# CH340T3R-R0.net
KiCad netlist of a schematic drawn in Altium Designer
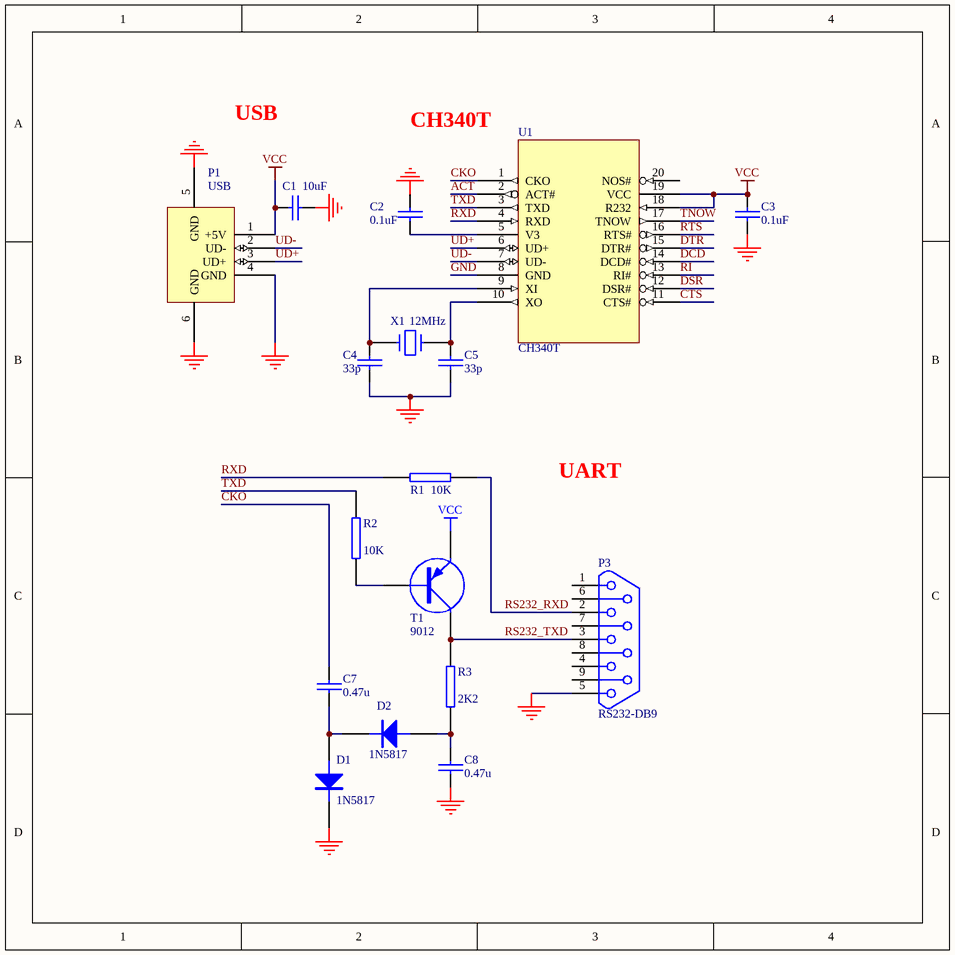
[diagram p0: CH340T3R-R0.SchDoc]

(export (version "E")
  (design (tool "Eeschema 10.0.6"))
  (components
    (comp (ref "C1")
      (value "10uF")
      (footprint "3216_C")
      (description "Capacitor")
      (libsource (lib "*") (part "CAP"))
    )
    (comp (ref "C2")
      (value "0.1uF")
      (footprint "0603_C")
      (description "Capacitor")
      (libsource (lib "*") (part "CAP"))
    )
    (comp (ref "C3")
      (value "0.1uF")
      (footprint "0603_C")
      (description "Capacitor")
      (libsource (lib "*") (part "CAP"))
    )
    (comp (ref "C4")
      (value "33p")
      (footprint "0603_C")
      (description "Capacitor")
      (libsource (lib "") (part "CAP_1"))
    )
    (comp (ref "C5")
      (value "33p")
      (footprint "0603_C")
      (description "Capacitor")
      (libsource (lib "") (part "CAP_1"))
    )
    (comp (ref "C7") (value "0.47u") (footprint "0603_C") (libsource (lib "*") (part "CPA")))
    (comp (ref "C8") (value "0.47u") (footprint "0603_C") (libsource (lib "*") (part "CPA")))
    (comp (ref "D1")
      (value "1N5817")
      (footprint "7227+")
      (description "Diode")
      (libsource (lib "*") (part "DIODE"))
    )
    (comp (ref "D2")
      (value "1N5817")
      (footprint "7227+")
      (description "Diode")
      (libsource (lib "*") (part "DIODE"))
    )
    (comp (ref "P1") (value "USB") (footprint "USBAM") (libsource (lib "*") (part "USB")))
    (comp (ref "P3")
      (value "RS232-DB9")
      (footprint "DB9-PAD-M")
      (libsource (lib "wch_sch_others") (part "DB9"))
    )
    (comp (ref "R1") (value "10K") (footprint "0603") (libsource (lib "*") (part "RES2")))
    (comp (ref "R2") (value "10K") (footprint "0603") (libsource (lib "*") (part "RES2")))
    (comp (ref "R3") (value "2K2") (footprint "0603") (libsource (lib "*") (part "RES2")))
    (comp (ref "T1")
      (value "9012")
      (footprint "SOT-23")
      (description "PNP Transistor")
      (libsource (lib "*") (part "PNP"))
    )
    (comp (ref "U1")
      (value "CH340T")
      (footprint "SSOP20")
      (description "USB to TTL Serial / UART,  USB to IrDA")
      (libsource (lib "CHXXX") (part "CH340T"))
    )
    (comp (ref "X1")
      (value "12MHz")
      (footprint "XT3225")
      (description "Crystal")
      (libsource (lib "*") (part "CRYSTAL"))
    )
  )
  (nets
    (net (code "1") (name "/ACT") (class "Default")
      (node (ref "U1") (pin "2") (pinfunction "ACT#_2") (pintype "output"))
    )
    (net (code "2") (name "/CKO") (class "Default")
      (node (ref "C7") (pin "2") (pintype "passive"))
      (node (ref "U1") (pin "1") (pinfunction "CKO_1") (pintype "output"))
    )
    (net (code "3") (name "/CTS") (class "Default")
      (node (ref "U1") (pin "11") (pinfunction "CTS#_11") (pintype "input"))
    )
    (net (code "4") (name "/DCD") (class "Default")
      (node (ref "U1") (pin "14") (pinfunction "DCD#_14") (pintype "input"))
    )
    (net (code "5") (name "/DSR") (class "Default")
      (node (ref "U1") (pin "12") (pinfunction "DSR#_12") (pintype "input"))
    )
    (net (code "6") (name "/DTR") (class "Default")
      (node (ref "U1") (pin "15") (pinfunction "DTR#_15") (pintype "output"))
    )
    (net (code "7") (name "/RI") (class "Default")
      (node (ref "U1") (pin "13") (pinfunction "RI#_13") (pintype "input"))
    )
    (net (code "8") (name "/RS232_RXD") (class "Default")
      (node (ref "P3") (pin "2") (pinfunction "2_2") (pintype "passive"))
      (node (ref "R1") (pin "2") (pinfunction "2_2") (pintype "passive"))
    )
    (net (code "9") (name "/RS232_TXD") (class "Default")
      (node (ref "P3") (pin "3") (pinfunction "3_3") (pintype "passive"))
      (node (ref "R3") (pin "2") (pinfunction "2_2") (pintype "passive"))
      (node (ref "T1") (pin "3") (pinfunction "C_3") (pintype "passive"))
    )
    (net (code "10") (name "/RTS") (class "Default")
      (node (ref "U1") (pin "16") (pinfunction "RTS#_16") (pintype "output"))
    )
    (net (code "11") (name "/RXD") (class "Default")
      (node (ref "R1") (pin "1") (pinfunction "1_1") (pintype "passive"))
      (node (ref "U1") (pin "4") (pinfunction "RXD_4") (pintype "input"))
    )
    (net (code "12") (name "/TNOW") (class "Default")
      (node (ref "U1") (pin "17") (pinfunction "TNOW_17") (pintype "output"))
    )
    (net (code "13") (name "/TXD") (class "Default")
      (node (ref "R2") (pin "2") (pinfunction "2_2") (pintype "passive"))
      (node (ref "U1") (pin "3") (pinfunction "TXD_3") (pintype "output"))
    )
    (net (code "14") (name "/UD+") (class "Default")
      (node (ref "P1") (pin "3") (pinfunction "UD+_3") (pintype "bidirectional"))
      (node (ref "U1") (pin "6") (pinfunction "UD+_6") (pintype "bidirectional"))
    )
    (net (code "15") (name "/UD-") (class "Default")
      (node (ref "P1") (pin "2") (pinfunction "UD-_2") (pintype "bidirectional"))
      (node (ref "U1") (pin "7") (pinfunction "UD-_7") (pintype "bidirectional"))
    )
    (net (code "16") (name "GND") (class "Default")
      (node (ref "C1") (pin "2") (pinfunction "2_2") (pintype "passive"))
      (node (ref "C2") (pin "2") (pinfunction "2_2") (pintype "passive"))
      (node (ref "C3") (pin "2") (pinfunction "2_2") (pintype "passive"))
      (node (ref "C4") (pin "2") (pinfunction "2_2") (pintype "passive"))
      (node (ref "C5") (pin "2") (pinfunction "2_2") (pintype "passive"))
      (node (ref "C8") (pin "2") (pintype "passive"))
      (node (ref "D1") (pin "2") (pinfunction "K_2") (pintype "passive"))
      (node (ref "P1") (pin "4") (pinfunction "GND_4") (pintype "power_in"))
      (node (ref "P1") (pin "5") (pinfunction "GND_5") (pintype "power_in"))
      (node (ref "P1") (pin "6") (pinfunction "GND_6") (pintype "power_in"))
      (node (ref "P3") (pin "5") (pinfunction "5_5") (pintype "passive"))
      (node (ref "U1") (pin "8") (pinfunction "GND_8") (pintype "power_in"))
    )
    (net (code "17") (name "Net-(D1-A)") (class "Default")
      (node (ref "C7") (pin "1") (pintype "passive"))
      (node (ref "D1") (pin "1") (pinfunction "A_1") (pintype "passive"))
      (node (ref "D2") (pin "2") (pinfunction "K_2") (pintype "passive"))
    )
    (net (code "18") (name "Net-(D2-A)") (class "Default")
      (node (ref "C8") (pin "1") (pintype "passive"))
      (node (ref "D2") (pin "1") (pinfunction "A_1") (pintype "passive"))
      (node (ref "R3") (pin "1") (pinfunction "1_1") (pintype "passive"))
    )
    (net (code "19") (name "Net-(T1-B)") (class "Default")
      (node (ref "R2") (pin "1") (pinfunction "1_1") (pintype "passive"))
      (node (ref "T1") (pin "1") (pinfunction "B_1") (pintype "passive"))
    )
    (net (code "20") (name "Net-(U1-V3)") (class "Default")
      (node (ref "C2") (pin "1") (pinfunction "1_1") (pintype "passive"))
      (node (ref "U1") (pin "5") (pinfunction "V3_5") (pintype "power_in"))
    )
    (net (code "21") (name "Net-(U1-XI)") (class "Default")
      (node (ref "C4") (pin "1") (pinfunction "1_1") (pintype "passive"))
      (node (ref "U1") (pin "9") (pinfunction "XI_9") (pintype "input"))
      (node (ref "X1") (pin "1") (pinfunction "1_1") (pintype "passive"))
    )
    (net (code "22") (name "Net-(U1-XO)") (class "Default")
      (node (ref "C5") (pin "1") (pinfunction "1_1") (pintype "passive"))
      (node (ref "U1") (pin "10") (pinfunction "XO_10") (pintype "output"))
      (node (ref "X1") (pin "3") (pinfunction "3_3") (pintype "passive"))
    )
    (net (code "23") (name "VCC") (class "Default")
      (node (ref "C1") (pin "1") (pinfunction "1_1") (pintype "passive"))
      (node (ref "C3") (pin "1") (pinfunction "1_1") (pintype "passive"))
      (node (ref "P1") (pin "1") (pinfunction "+5V_1") (pintype "power_in"))
      (node (ref "T1") (pin "2") (pinfunction "E_2") (pintype "passive"))
      (node (ref "U1") (pin "18") (pinfunction "R232_18") (pintype "input"))
      (node (ref "U1") (pin "19") (pinfunction "VCC_19") (pintype "power_in"))
    )
    (net (code "24") (name "unconnected-(P3-Pad1)") (class "Default")
      (node (ref "P3") (pin "1") (pinfunction "1_1") (pintype "passive"))
    )
    (net (code "25") (name "unconnected-(P3-Pad4)") (class "Default")
      (node (ref "P3") (pin "4") (pinfunction "4_4") (pintype "passive"))
    )
    (net (code "26") (name "unconnected-(P3-Pad6)") (class "Default")
      (node (ref "P3") (pin "6") (pinfunction "6_6") (pintype "passive"))
    )
    (net (code "27") (name "unconnected-(P3-Pad7)") (class "Default")
      (node (ref "P3") (pin "7") (pinfunction "7_7") (pintype "passive"))
    )
    (net (code "28") (name "unconnected-(P3-Pad8)") (class "Default")
      (node (ref "P3") (pin "8") (pinfunction "8_8") (pintype "passive"))
    )
    (net (code "29") (name "unconnected-(P3-Pad9)") (class "Default")
      (node (ref "P3") (pin "9") (pinfunction "9_9") (pintype "passive"))
    )
    (net (code "30") (name "unconnected-(U1-NOS#-Pad20)") (class "Default")
      (node (ref "U1") (pin "20") (pinfunction "NOS#_20") (pintype "input"))
    )
  )
)
